# SCH_Hackclub-nfc-buisness-card_2025-03-3.net
KiCad netlist of a schematic drawn in EasyEDA
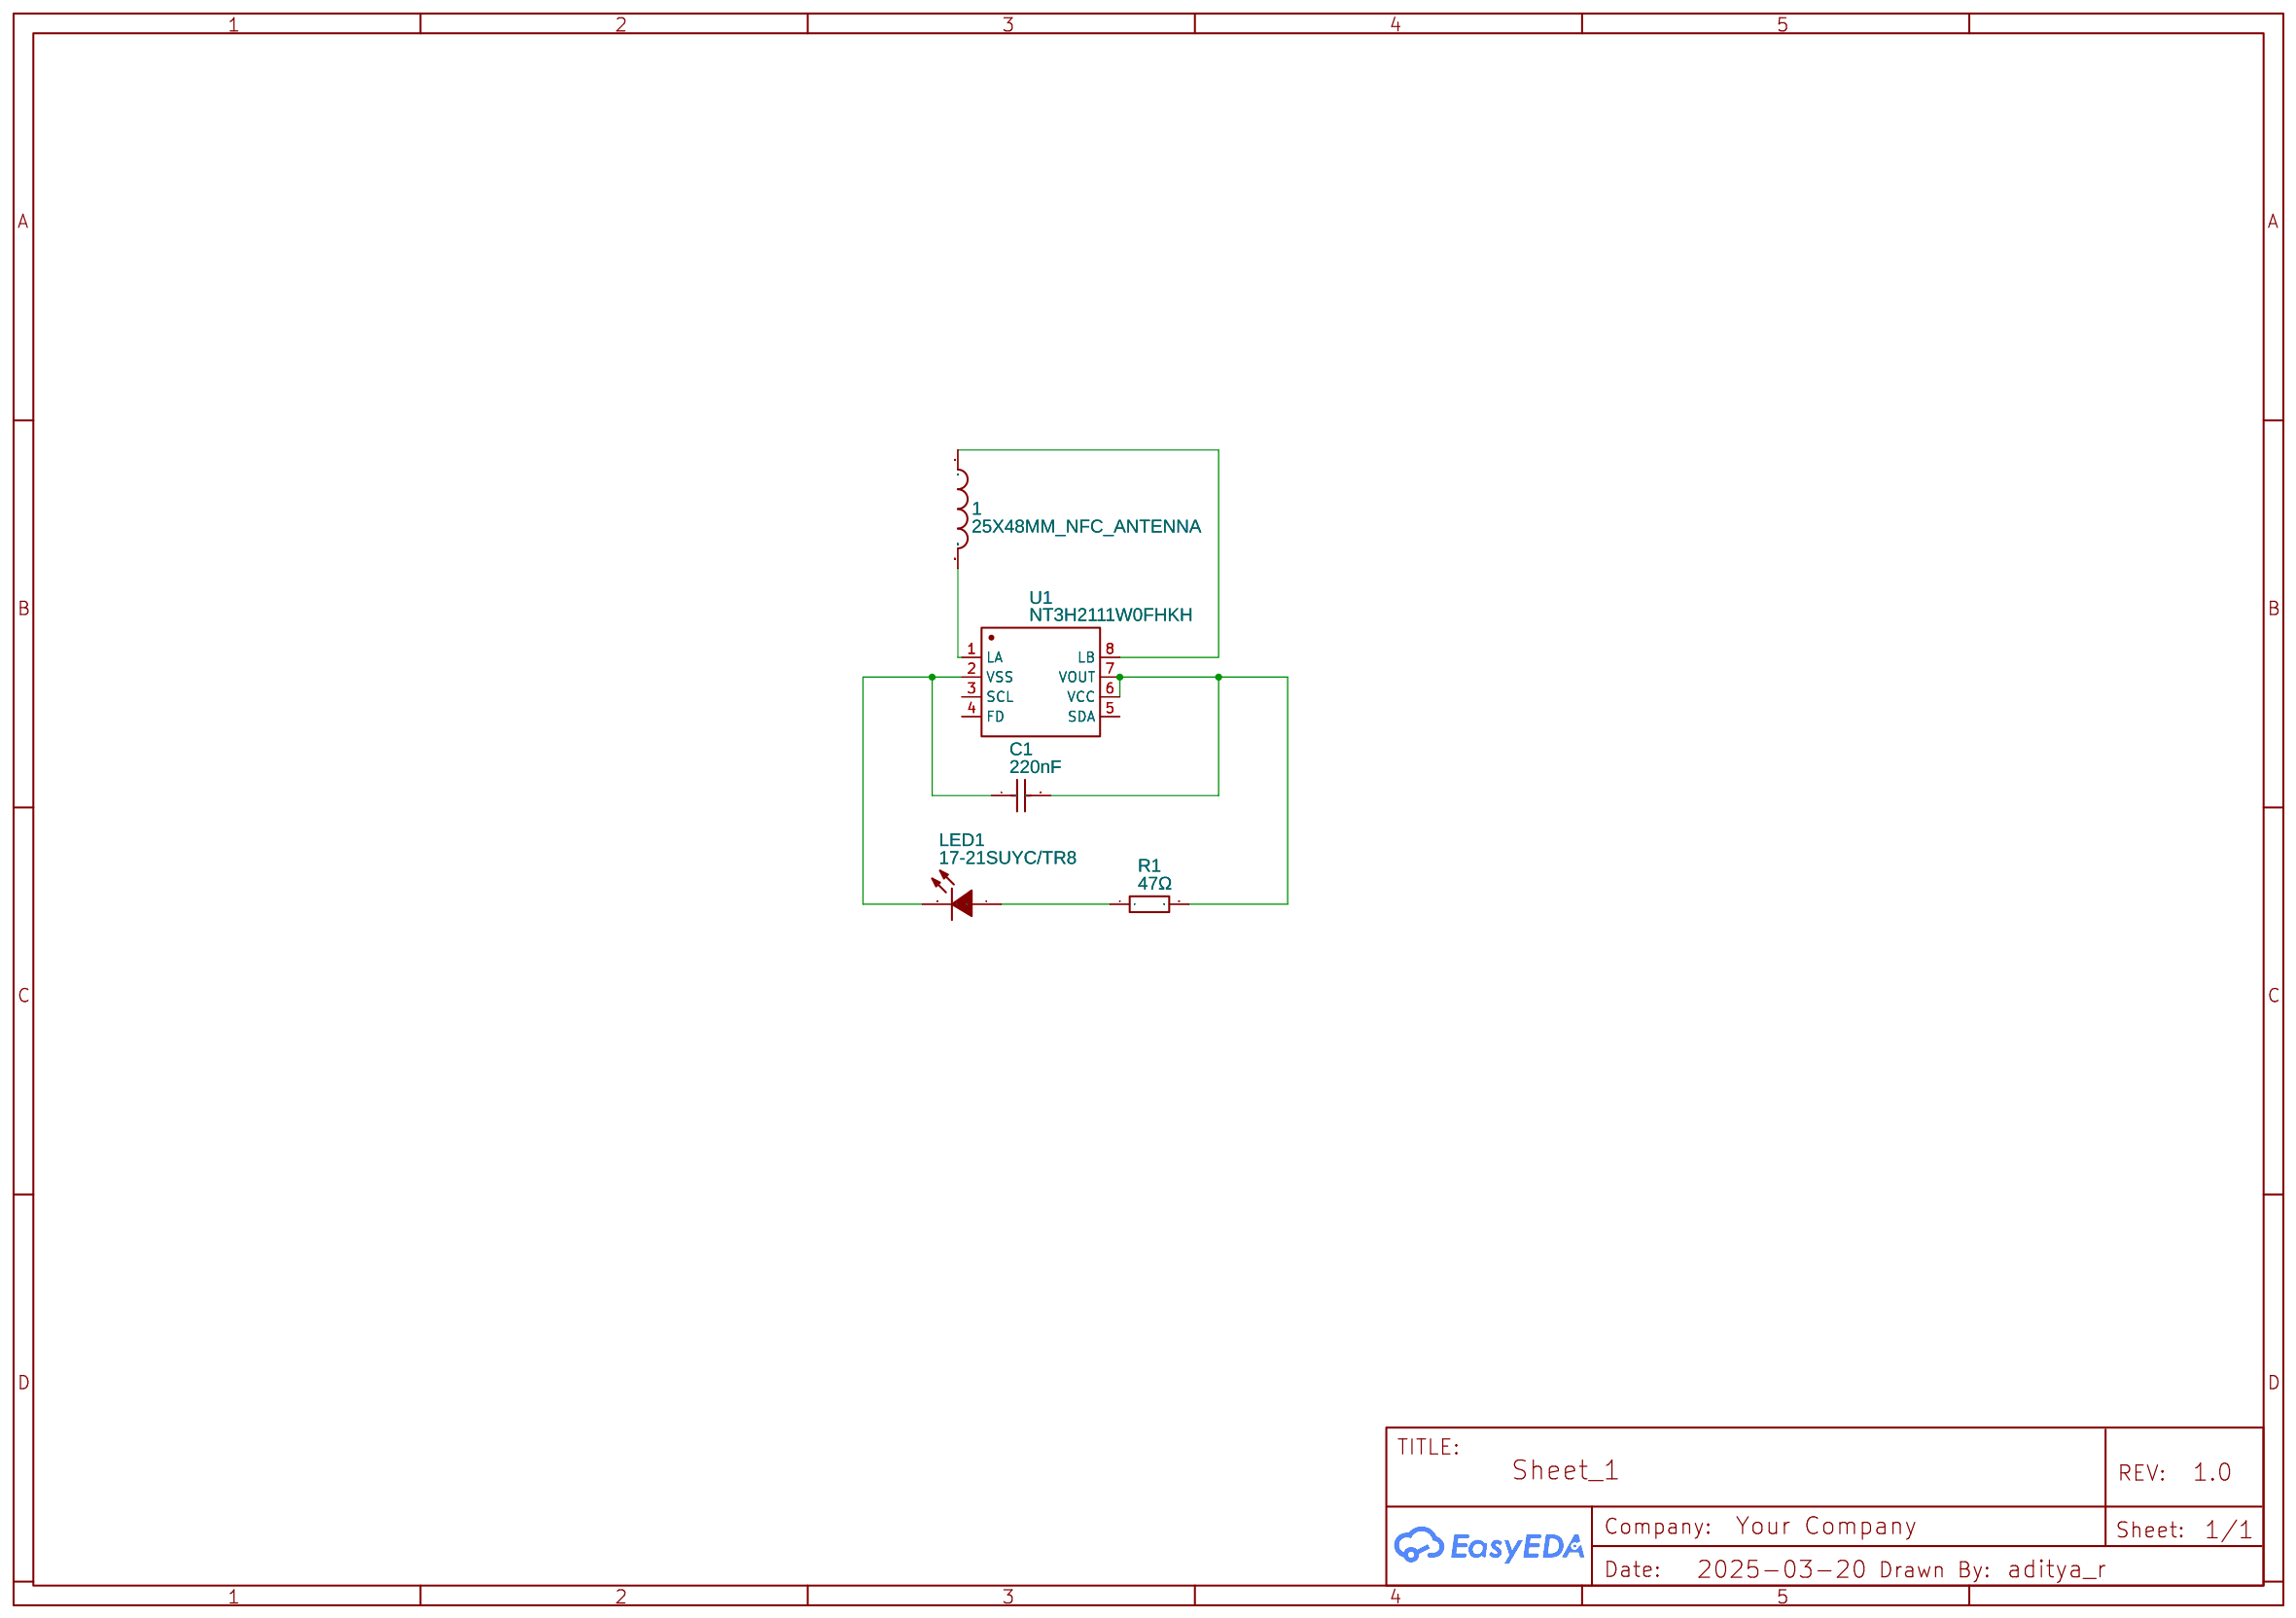
[diagram p0: schematic sheet]

(export (version "E")
  (design (tool "Eeschema 10.0.6"))
  (components
    (comp (ref "1") (value "25X48MM_NFC_ANTENNA") (libsource (lib "") (part "25X48MM_NFC_ANTENNA")))
    (comp (ref "C1")
      (value "220nF")
      (fields
        (field (name "Manufacturer Part") "CL10B224KA8NNNC")
        (field (name "Manufacturer") "SAMSUNG(三星)")
      )
      (libsource (lib "") (part "CL10B224KA8NNNC"))
    )
    (comp (ref "LED1")
      (value "17-21SUYC/TR8")
      (fields (field (name "Manufacturer Part") "KT-0805黄灯") (field (name "Manufacturer") "KENTO"))
      (libsource (lib "") (part "17-21SUYC/TR8"))
    )
    (comp (ref "R1")
      (value "47Ω")
      (fields
        (field (name "Manufacturer Part") "0603WAF470JT5E")
        (field (name "Manufacturer") "UNI-ROYAL(厚声)")
      )
      (libsource (lib "") (part "0603WAF470JT5E"))
    )
    (comp (ref "U1")
      (value "NT3H2111W0FHKH")
      (fields (field (name "Manufacturer") "NXP(恩智浦)"))
      (libsource (lib "") (part "NT3H2111W0FHKH"))
    )
  )
  (nets
    (net (code "1") (name "Net-(LED1-+)") (class "Default")
      (node (ref "LED1") (pin "1") (pinfunction "+_1") (pintype "unspecified"))
      (node (ref "R1") (pin "1") (pinfunction "1_1") (pintype "input"))
    )
    (net (code "2") (name "Net-(LED1--)") (class "Default")
      (node (ref "C1") (pin "1") (pinfunction "1_1") (pintype "input"))
      (node (ref "LED1") (pin "2") (pinfunction "-_2") (pintype "unspecified"))
      (node (ref "U1") (pin "2") (pinfunction "VSS_2") (pintype "unspecified"))
    )
    (net (code "3") (name "Net-(U1-LA)") (class "Default")
      (node (ref "1") (pin "P$2") (pinfunction "P$2_P$2") (pintype "bidirectional"))
      (node (ref "U1") (pin "1") (pinfunction "LA_1") (pintype "unspecified"))
    )
    (net (code "4") (name "Net-(U1-LB)") (class "Default")
      (node (ref "1") (pin "P$1") (pinfunction "P$1_P$1") (pintype "bidirectional"))
      (node (ref "U1") (pin "8") (pinfunction "LB_8") (pintype "unspecified"))
    )
    (net (code "5") (name "Net-(U1-VCC)") (class "Default")
      (node (ref "C1") (pin "2") (pinfunction "2_2") (pintype "input"))
      (node (ref "R1") (pin "2") (pinfunction "2_2") (pintype "input"))
      (node (ref "U1") (pin "6") (pinfunction "VCC_6") (pintype "unspecified"))
      (node (ref "U1") (pin "7") (pinfunction "VOUT_7") (pintype "unspecified"))
    )
    (net (code "6") (name "unconnected-(U1-FD-Pad4)") (class "Default")
      (node (ref "U1") (pin "4") (pinfunction "FD_4") (pintype "unspecified"))
    )
    (net (code "7") (name "unconnected-(U1-SCL-Pad3)") (class "Default")
      (node (ref "U1") (pin "3") (pinfunction "SCL_3") (pintype "unspecified"))
    )
    (net (code "8") (name "unconnected-(U1-SDA-Pad5)") (class "Default")
      (node (ref "U1") (pin "5") (pinfunction "SDA_5") (pintype "unspecified"))
    )
  )
)
